# 2024-08-19.net
KiCad netlist of a schematic drawn in Altium Designer
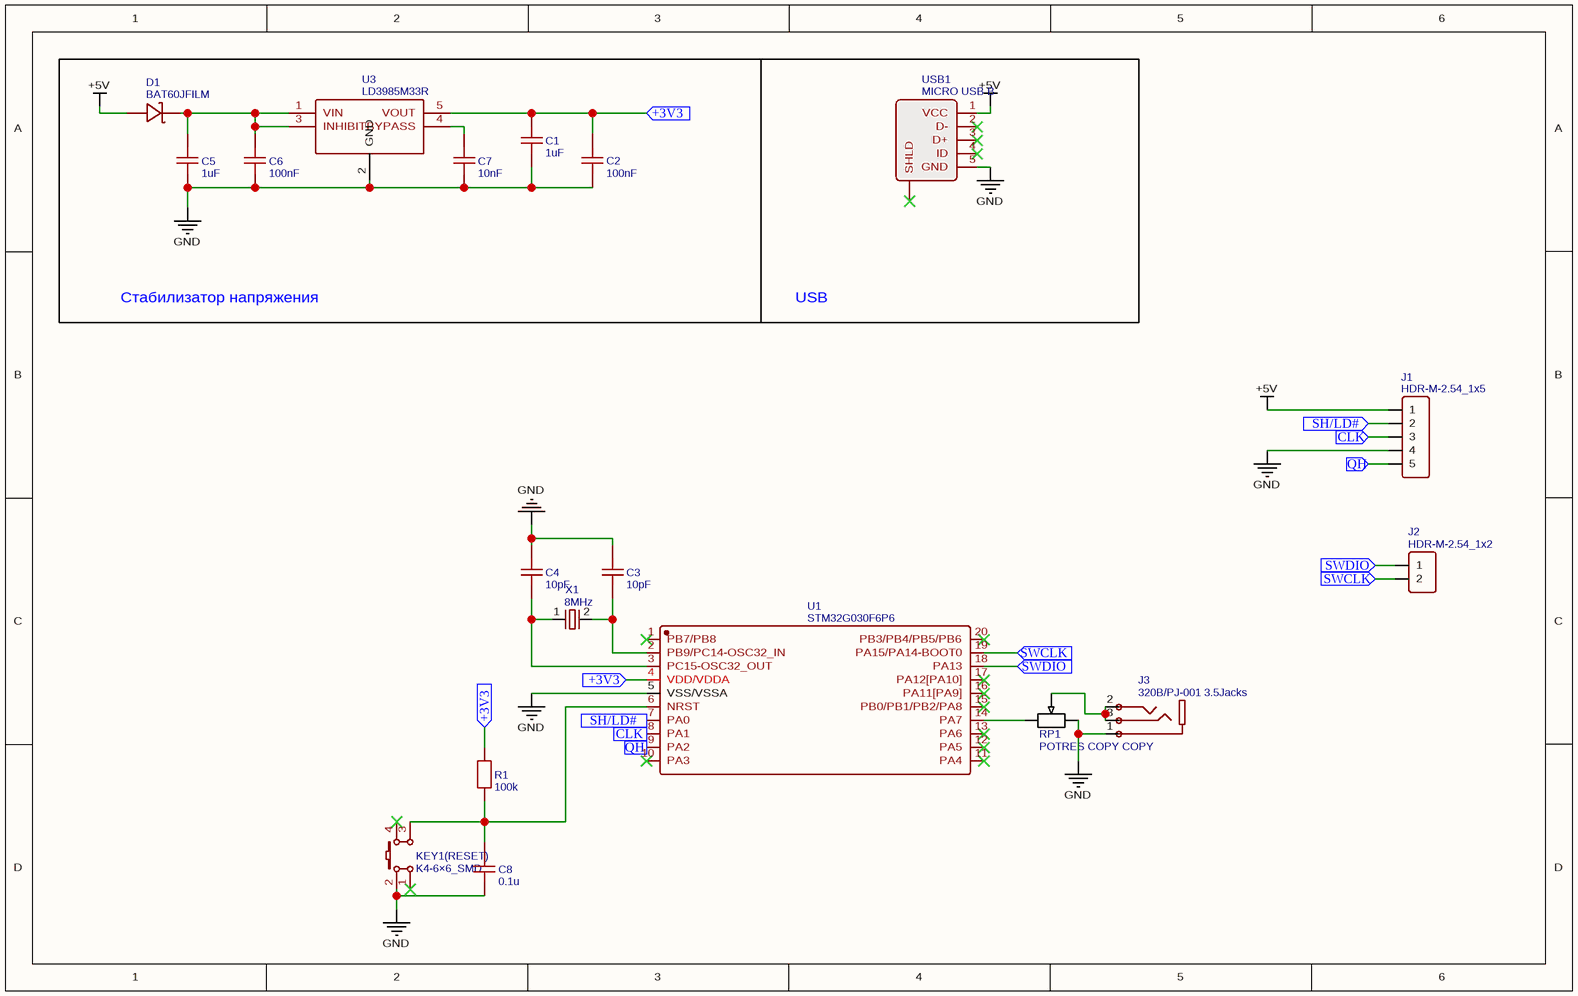
[diagram p0: Микроконтроллер_2024-08-19.schdoc]

(export (version "E")
  (design (tool "Eeschema 10.0.6"))
  (components
    (comp (ref "C1")
      (value "1uF")
      (fields (field (name "CONTRIBUTOR") "LCEDA_Lib"))
      (libsource (lib "altium-import") (part "root_1_1uF_"))
    )
    (comp (ref "C2")
      (value "100nF")
      (fields (field (name "CONTRIBUTOR") "LCEDA_Lib"))
      (libsource (lib "altium-import") (part "root_1_100nF_"))
    )
    (comp (ref "C3")
      (value "10pF")
      (fields (field (name "CONTRIBUTOR") "LCEDA_Lib"))
      (libsource (lib "altium-import") (part "root_3_10pF_"))
    )
    (comp (ref "C4")
      (value "10pF")
      (fields (field (name "CONTRIBUTOR") "LCEDA_Lib"))
      (libsource (lib "altium-import") (part "root_3_10pF_"))
    )
    (comp (ref "C5")
      (value "1uF")
      (fields (field (name "CONTRIBUTOR") "LCEDA_Lib"))
      (libsource (lib "altium-import") (part "root_1_1uF_"))
    )
    (comp (ref "C6")
      (value "100nF")
      (fields (field (name "CONTRIBUTOR") "LCEDA_Lib"))
      (libsource (lib "altium-import") (part "root_1_100nF_"))
    )
    (comp (ref "C7")
      (value "10nF")
      (fields (field (name "CONTRIBUTOR") "LCEDA_Lib"))
      (libsource (lib "altium-import") (part "root_1_10nF_"))
    )
    (comp (ref "C8")
      (value "0.1u")
      (fields (field (name "CONTRIBUTOR") "LCEDA_Lib"))
      (libsource (lib "altium-import") (part "root_1_0.1u_"))
    )
    (comp (ref "D1")
      (value "BAT60JFILM")
      (fields (field (name "MANUFACTURER") "ST(意法半导体)") (field (name "CONTRIBUTOR") "LCSC"))
      (libsource (lib "altium-import") (part "root_2_BAT60JFILM_"))
    )
    (comp (ref "J1")
      (value "HDR-M-2.54_1x5")
      (fields (field (name "CONTRIBUTOR") "LCEDA_Lib"))
      (libsource (lib "altium-import") (part "root_0_HDR-M-2.54_1x5_"))
    )
    (comp (ref "J2")
      (value "HDR-M-2.54_1x2")
      (fields (field (name "CONTRIBUTOR") "LCEDA_Lib"))
      (libsource (lib "altium-import") (part "root_0_HDR-M-2.54_1x2_"))
    )
    (comp (ref "J3")
      (value "320B/PJ-001 3.5Jacks")
      (fields (field (name "MANUFACTURER") "ReliaPro"))
      (libsource (lib "altium-import") (part "root_2_320B/PJ-001 3.5Jacks_"))
    )
    (comp (ref "KEY1(RESET)")
      (value "K4-6×6_SMD")
      (fields
        (field (name "MANUFACTURER") "韩国韩荣")
        (field (name "MANUFACTURER PART") "K2-6639SP-D4SC-04")
        (field (name "CONTRIBUTOR") "LCEDA_Lib")
      )
      (libsource (lib "altium-import") (part "root_1_K4-6×6_SMD_"))
    )
    (comp (ref "R1")
      (value "100k")
      (fields (field (name "CONTRIBUTOR") "LCEDA_Lib"))
      (libsource (lib "altium-import") (part "root_1_100k_"))
    )
    (comp (ref "RP1")
      (value "POTRES COPY COPY")
      (fields (field (name "CONTRIBUTOR") "ttnigmatyllin"))
      (libsource (lib "altium-import") (part "root_0_POTRES COPY COPY_"))
    )
    (comp (ref "U1")
      (value "STM32G030F6P6")
      (fields (field (name "MANUFACTURER") "ST(意法半导体)") (field (name "CONTRIBUTOR") "LCSC"))
      (libsource (lib "altium-import") (part "root_0_STM32G030F6P6_"))
    )
    (comp (ref "U3")
      (value "LD3985M33R")
      (fields (field (name "MANUFACTURER") "ST(意法半导体)"))
      (libsource (lib "altium-import") (part "root_0_LD3985M33R_"))
    )
    (comp (ref "USB1")
      (value "MICRO USB B")
      (fields (field (name "MANUFACTURER") "HRO") (field (name "MANUFACTURER PART") "U-F-M5SW-Y-3"))
      (libsource (lib "altium-import") (part "root_0_MICRO USB B_"))
    )
    (comp (ref "X1")
      (value "8MHz")
      (fields
        (field (name "MANUFACTURER") "NDK")
        (field (name "MANUFACTURER PART") "NX3225GD-8MHZ-STD-CRA-3")
        (field (name "CONTRIBUTOR") "LCSC")
      )
      (libsource (lib "altium-import") (part "root_0_8MHz_"))
    )
  )
  (nets
    (net (code "1") (name "+5V") (class "Default")
      (node (ref "D1") (pin "2") (pinfunction "A_2") (pintype "passive"))
      (node (ref "J1") (pin "1") (pinfunction "1_1") (pintype "passive"))
      (node (ref "USB1") (pin "1") (pinfunction "VCC_1") (pintype "passive"))
    )
    (net (code "2") (name "/+3V3") (class "Default")
      (node (ref "C1") (pin "2") (pinfunction "2_2") (pintype "passive"))
      (node (ref "C2") (pin "2") (pinfunction "2_2") (pintype "passive"))
      (node (ref "R1") (pin "2") (pinfunction "2_2") (pintype "passive"))
      (node (ref "U1") (pin "4") (pinfunction "VDD/VDDA_4") (pintype "passive"))
      (node (ref "U3") (pin "5") (pinfunction "VOUT_5") (pintype "passive"))
    )
    (net (code "3") (name "/CLK") (class "Default")
      (node (ref "J1") (pin "3") (pinfunction "3_3") (pintype "passive"))
      (node (ref "U1") (pin "8") (pinfunction "PA1_8") (pintype "passive"))
    )
    (net (code "4") (name "/QH") (class "Default")
      (node (ref "J1") (pin "5") (pinfunction "5_5") (pintype "passive"))
      (node (ref "U1") (pin "9") (pinfunction "PA2_9") (pintype "passive"))
    )
    (net (code "5") (name "/SH{slash}LD#") (class "Default")
      (node (ref "J1") (pin "2") (pinfunction "2_2") (pintype "passive"))
      (node (ref "U1") (pin "7") (pinfunction "PA0_7") (pintype "passive"))
    )
    (net (code "6") (name "/SWCLK") (class "Default")
      (node (ref "J2") (pin "2") (pinfunction "2_2") (pintype "passive"))
      (node (ref "U1") (pin "19") (pinfunction "PA15/PA14-BOOT0_19") (pintype "passive"))
    )
    (net (code "7") (name "/SWDIO") (class "Default")
      (node (ref "J2") (pin "1") (pinfunction "1_1") (pintype "passive"))
      (node (ref "U1") (pin "18") (pinfunction "PA13_18") (pintype "passive"))
    )
    (net (code "8") (name "GND") (class "Default")
      (node (ref "C1") (pin "1") (pinfunction "1_1") (pintype "passive"))
      (node (ref "C2") (pin "1") (pinfunction "1_1") (pintype "passive"))
      (node (ref "C3") (pin "1") (pinfunction "1_1") (pintype "passive"))
      (node (ref "C4") (pin "1") (pinfunction "1_1") (pintype "passive"))
      (node (ref "C5") (pin "1") (pinfunction "1_1") (pintype "passive"))
      (node (ref "C6") (pin "1") (pinfunction "1_1") (pintype "passive"))
      (node (ref "C7") (pin "1") (pinfunction "1_1") (pintype "passive"))
      (node (ref "C8") (pin "1") (pinfunction "1_1") (pintype "passive"))
      (node (ref "J1") (pin "4") (pinfunction "4_4") (pintype "passive"))
      (node (ref "J3") (pin "1") (pinfunction "1_1") (pintype "passive"))
      (node (ref "KEY1(RESET)") (pin "2") (pinfunction "2_2") (pintype "passive"))
      (node (ref "RP1") (pin "3") (pinfunction "3_3") (pintype "passive"))
      (node (ref "U1") (pin "5") (pinfunction "VSS/VSSA_5") (pintype "passive"))
      (node (ref "U3") (pin "2") (pinfunction "GND_2") (pintype "passive"))
      (node (ref "USB1") (pin "5") (pinfunction "GND_5") (pintype "passive"))
    )
    (net (code "9") (name "Net-(D1-K)") (class "Default")
      (node (ref "C5") (pin "2") (pinfunction "2_2") (pintype "passive"))
      (node (ref "C6") (pin "2") (pinfunction "2_2") (pintype "passive"))
      (node (ref "D1") (pin "1") (pinfunction "K_1") (pintype "passive"))
      (node (ref "U3") (pin "1") (pinfunction "VIN_1") (pintype "passive"))
      (node (ref "U3") (pin "3") (pinfunction "INHIBIT_3") (pintype "passive"))
    )
    (net (code "10") (name "Net-(J3-Pad2)") (class "Default")
      (node (ref "J3") (pin "2") (pinfunction "2_2") (pintype "passive"))
      (node (ref "J3") (pin "3") (pinfunction "3_3") (pintype "passive"))
      (node (ref "RP1") (pin "2") (pinfunction "2_2") (pintype "passive"))
    )
    (net (code "11") (name "Net-(U1-NRST)") (class "Default")
      (node (ref "C8") (pin "2") (pinfunction "2_2") (pintype "passive"))
      (node (ref "KEY1(RESET)") (pin "3") (pinfunction "3_3") (pintype "passive"))
      (node (ref "R1") (pin "1") (pinfunction "1_1") (pintype "passive"))
      (node (ref "U1") (pin "6") (pinfunction "NRST_6") (pintype "passive"))
    )
    (net (code "12") (name "Net-(U1-PA7)") (class "Default")
      (node (ref "RP1") (pin "1") (pinfunction "1_1") (pintype "passive"))
      (node (ref "U1") (pin "14") (pinfunction "PA7_14") (pintype "passive"))
    )
    (net (code "13") (name "Net-(U1-PB9{slash}PC14-OSC32_IN)") (class "Default")
      (node (ref "C3") (pin "2") (pinfunction "2_2") (pintype "passive"))
      (node (ref "U1") (pin "2") (pinfunction "PB9/PC14-OSC32_IN_2") (pintype "passive"))
      (node (ref "X1") (pin "2") (pinfunction "GND_2") (pintype "passive"))
    )
    (net (code "14") (name "Net-(U1-PC15-OSC32_OUT)") (class "Default")
      (node (ref "C4") (pin "2") (pinfunction "2_2") (pintype "passive"))
      (node (ref "U1") (pin "3") (pinfunction "PC15-OSC32_OUT_3") (pintype "passive"))
      (node (ref "X1") (pin "1") (pinfunction "1_1") (pintype "passive"))
    )
    (net (code "15") (name "Net-(U3-BYPASS)") (class "Default")
      (node (ref "C7") (pin "2") (pinfunction "2_2") (pintype "passive"))
      (node (ref "U3") (pin "4") (pinfunction "BYPASS_4") (pintype "passive"))
    )
    (net (code "16") (name "unconnected-(KEY1(RESET)-Pad1)") (class "Default")
      (node (ref "KEY1(RESET)") (pin "1") (pinfunction "1_1") (pintype "passive+no_connect"))
    )
    (net (code "17") (name "unconnected-(KEY1(RESET)-Pad4)") (class "Default")
      (node (ref "KEY1(RESET)") (pin "4") (pinfunction "4_4") (pintype "passive+no_connect"))
    )
    (net (code "18") (name "unconnected-(U1-PA3-Pad10)") (class "Default")
      (node (ref "U1") (pin "10") (pinfunction "PA3_10") (pintype "passive+no_connect"))
    )
    (net (code "19") (name "unconnected-(U1-PA4-Pad11)") (class "Default")
      (node (ref "U1") (pin "11") (pinfunction "PA4_11") (pintype "passive+no_connect"))
    )
    (net (code "20") (name "unconnected-(U1-PA5-Pad12)") (class "Default")
      (node (ref "U1") (pin "12") (pinfunction "PA5_12") (pintype "passive+no_connect"))
    )
    (net (code "21") (name "unconnected-(U1-PA6-Pad13)") (class "Default")
      (node (ref "U1") (pin "13") (pinfunction "PA6_13") (pintype "passive+no_connect"))
    )
    (net (code "22") (name "unconnected-(U1-PA11[PA9]-Pad16)") (class "Default")
      (node (ref "U1") (pin "16") (pinfunction "PA11[PA9]_16") (pintype "passive+no_connect"))
    )
    (net (code "23") (name "unconnected-(U1-PA12[PA10]-Pad17)") (class "Default")
      (node (ref "U1") (pin "17") (pinfunction "PA12[PA10]_17") (pintype "passive+no_connect"))
    )
    (net (code "24") (name "unconnected-(U1-PB0{slash}PB1{slash}PB2{slash}PA8-Pad15)") (class "Default")
      (node (ref "U1") (pin "15") (pinfunction "PB0/PB1/PB2/PA8_15") (pintype "passive+no_connect"))
    )
    (net (code "25") (name "unconnected-(U1-PB3{slash}PB4{slash}PB5{slash}PB6-Pad20)") (class "Default")
      (node (ref "U1") (pin "20") (pinfunction "PB3/PB4/PB5/PB6_20") (pintype "passive+no_connect"))
    )
    (net (code "26") (name "unconnected-(U1-PB7{slash}PB8-Pad1)") (class "Default")
      (node (ref "U1") (pin "1") (pinfunction "PB7/PB8_1") (pintype "passive+no_connect"))
    )
    (net (code "27") (name "unconnected-(USB1-D+-Pad3)") (class "Default")
      (node (ref "USB1") (pin "3") (pinfunction "D+_3") (pintype "passive+no_connect"))
    )
    (net (code "28") (name "unconnected-(USB1-D--Pad2)") (class "Default")
      (node (ref "USB1") (pin "2") (pinfunction "D-_2") (pintype "passive+no_connect"))
    )
    (net (code "29") (name "unconnected-(USB1-ID-Pad4)") (class "Default")
      (node (ref "USB1") (pin "4") (pinfunction "ID_4") (pintype "passive+no_connect"))
    )
    (net (code "30") (name "unconnected-(USB1-SHLD-Pad6)") (class "Default")
      (node (ref "USB1") (pin "6") (pinfunction "SHLD_6") (pintype "passive+no_connect"))
    )
  )
)
